# SAME70N21-CU.net
KiCad netlist of a schematic drawn in EAGLE
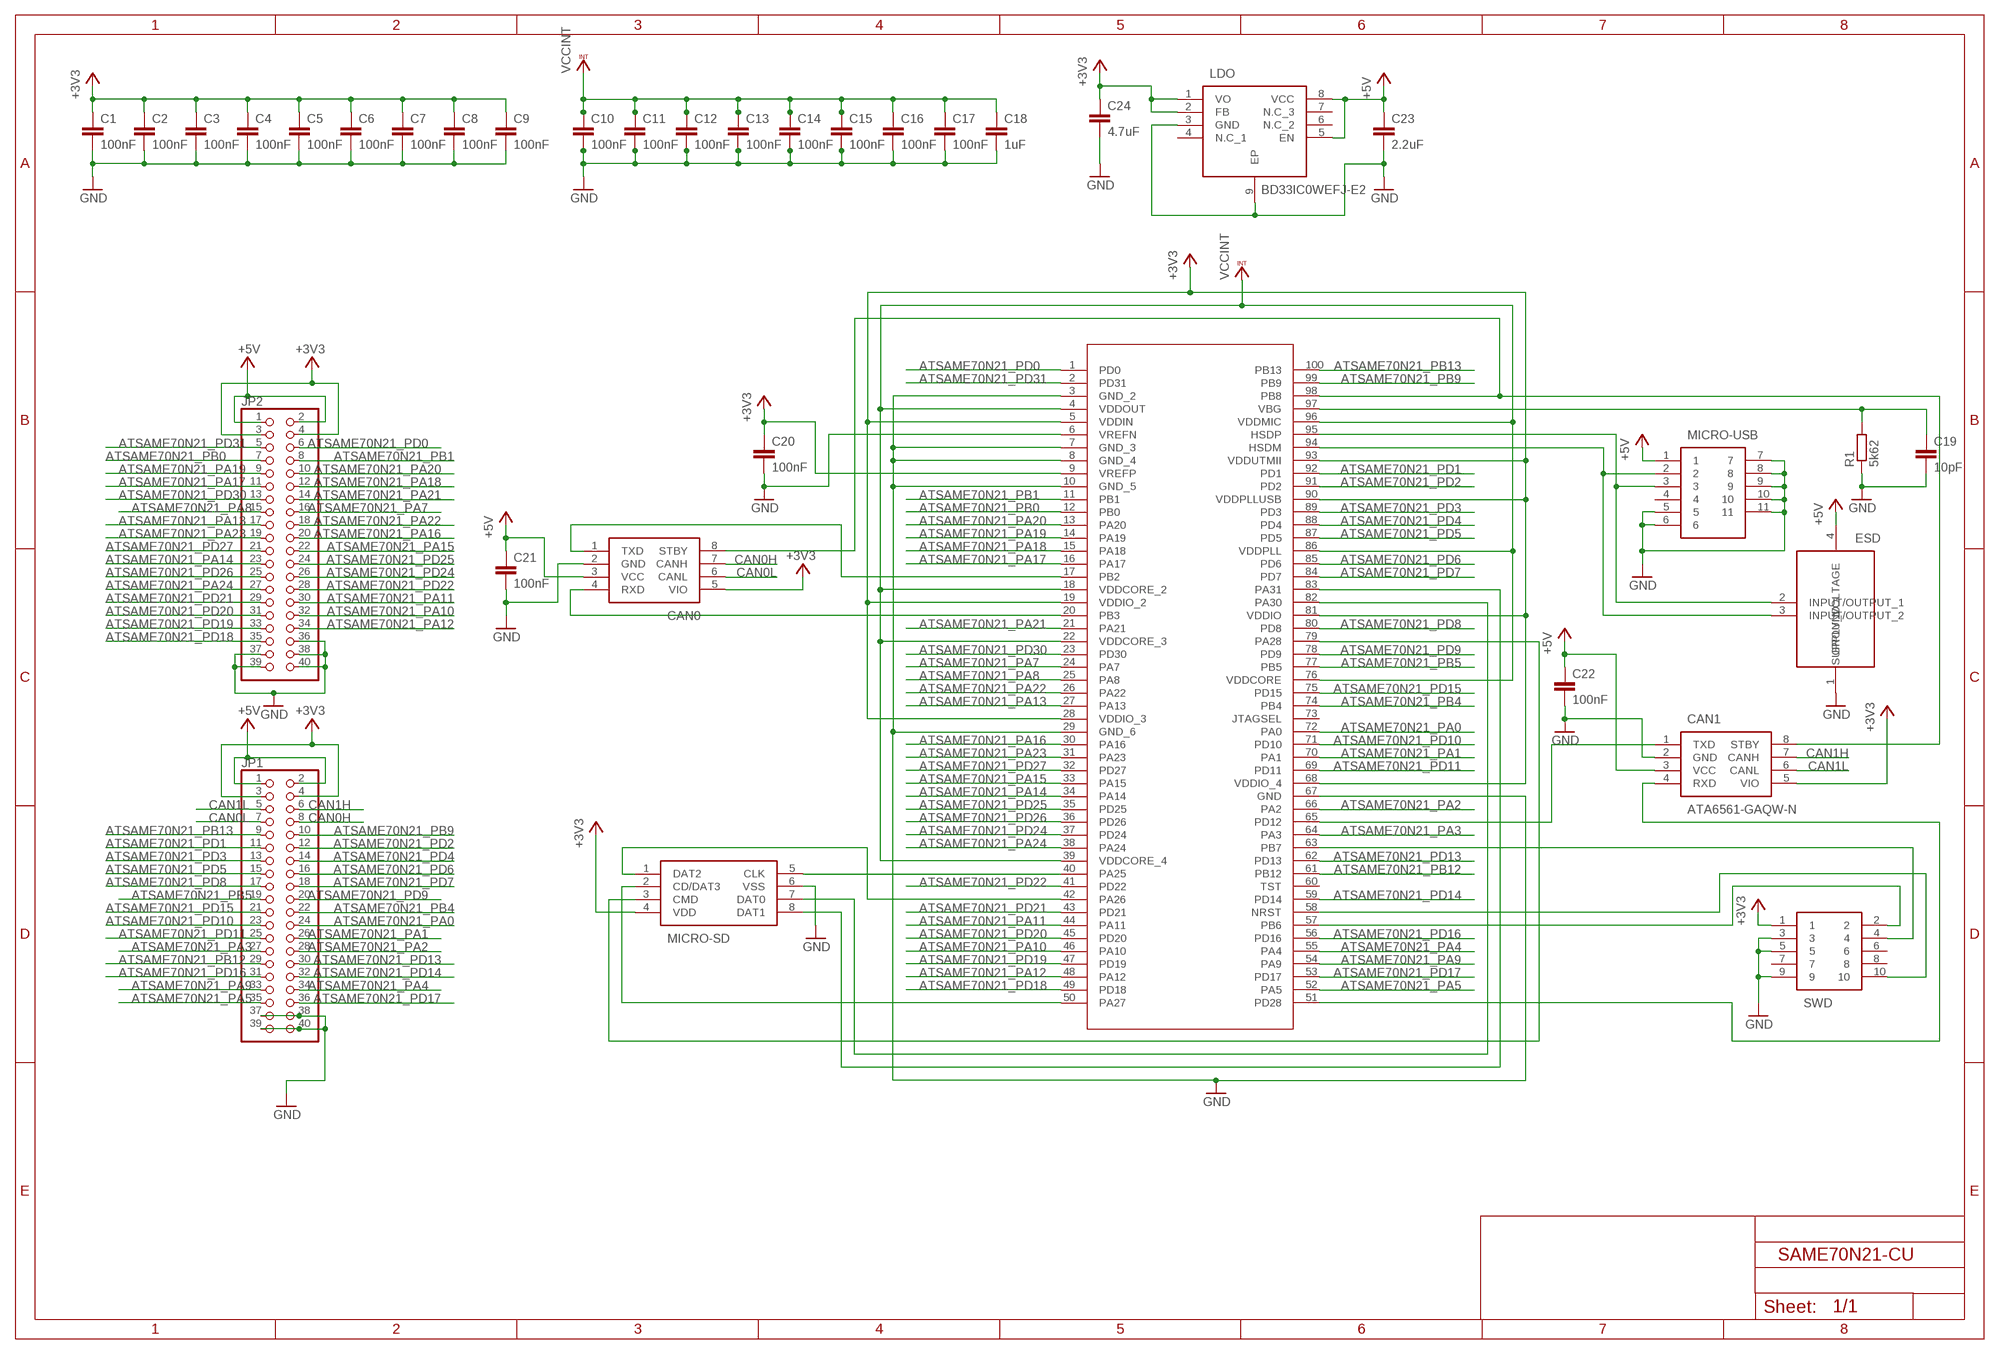
[diagram p0: schematic, sheet 1]

(export (version "E")
  (design (tool "Eeschema 10.0.6"))
  (components
    (comp (ref "C1")
      (value "100nF")
      (footprint "eagle-import:C1206")
      (libsource (lib "eagle-import") (part "C-EUC1206"))
    )
    (comp (ref "C2")
      (value "100nF")
      (footprint "eagle-import:C1206")
      (libsource (lib "eagle-import") (part "C-EUC1206"))
    )
    (comp (ref "C3")
      (value "100nF")
      (footprint "eagle-import:C1206")
      (libsource (lib "eagle-import") (part "C-EUC1206"))
    )
    (comp (ref "C4")
      (value "100nF")
      (footprint "eagle-import:C1206")
      (libsource (lib "eagle-import") (part "C-EUC1206"))
    )
    (comp (ref "C5")
      (value "100nF")
      (footprint "eagle-import:C1206")
      (libsource (lib "eagle-import") (part "C-EUC1206"))
    )
    (comp (ref "C6")
      (value "100nF")
      (footprint "eagle-import:C1206")
      (libsource (lib "eagle-import") (part "C-EUC1206"))
    )
    (comp (ref "C7")
      (value "100nF")
      (footprint "eagle-import:C1206")
      (libsource (lib "eagle-import") (part "C-EUC1206"))
    )
    (comp (ref "C8")
      (value "100nF")
      (footprint "eagle-import:C1206")
      (libsource (lib "eagle-import") (part "C-EUC1206"))
    )
    (comp (ref "C9")
      (value "100nF")
      (footprint "eagle-import:C1206")
      (libsource (lib "eagle-import") (part "C-EUC1206"))
    )
    (comp (ref "C10")
      (value "100nF")
      (footprint "eagle-import:C1206")
      (libsource (lib "eagle-import") (part "C-EUC1206"))
    )
    (comp (ref "C11")
      (value "100nF")
      (footprint "eagle-import:C1206")
      (libsource (lib "eagle-import") (part "C-EUC1206"))
    )
    (comp (ref "C12")
      (value "100nF")
      (footprint "eagle-import:C1206")
      (libsource (lib "eagle-import") (part "C-EUC1206"))
    )
    (comp (ref "C13")
      (value "100nF")
      (footprint "eagle-import:C1206")
      (libsource (lib "eagle-import") (part "C-EUC1206"))
    )
    (comp (ref "C14")
      (value "100nF")
      (footprint "eagle-import:C1206")
      (libsource (lib "eagle-import") (part "C-EUC1206"))
    )
    (comp (ref "C15")
      (value "100nF")
      (footprint "eagle-import:C1206")
      (libsource (lib "eagle-import") (part "C-EUC1206"))
    )
    (comp (ref "C16")
      (value "100nF")
      (footprint "eagle-import:C1206")
      (libsource (lib "eagle-import") (part "C-EUC1206"))
    )
    (comp (ref "C17")
      (value "100nF")
      (footprint "eagle-import:C1206")
      (libsource (lib "eagle-import") (part "C-EUC1206"))
    )
    (comp (ref "C18")
      (value "1uF")
      (footprint "eagle-import:C1206")
      (libsource (lib "eagle-import") (part "C-EUC1206"))
    )
    (comp (ref "C19")
      (value "10pF")
      (footprint "eagle-import:C1206")
      (libsource (lib "eagle-import") (part "C-EUC1206"))
    )
    (comp (ref "C20")
      (value "100nF")
      (footprint "eagle-import:C1206")
      (libsource (lib "eagle-import") (part "C-EUC1206"))
    )
    (comp (ref "C21")
      (value "100nF")
      (footprint "eagle-import:C1206")
      (libsource (lib "eagle-import") (part "C-EUC1206"))
    )
    (comp (ref "C22")
      (value "100nF")
      (footprint "eagle-import:C1206")
      (libsource (lib "eagle-import") (part "C-EUC1206"))
    )
    (comp (ref "C23")
      (value "2.2uF")
      (footprint "eagle-import:C1206")
      (libsource (lib "eagle-import") (part "C-EUC1206"))
    )
    (comp (ref "C24")
      (value "4.7uF")
      (footprint "eagle-import:C1206")
      (libsource (lib "eagle-import") (part "C-EUC1206"))
    )
    (comp (ref "CAN0")
      (value "ATA6561-GAQW-N")
      (footprint "eagle-import:SOIC127P600X175-8N")
      (fields (field (name "MOUSER_PART_NUMBER") "579-ATA6561-GAQW-N"))
      (libsource (lib "eagle-import") (part "ATA6561-GAQW-N"))
    )
    (comp (ref "CAN1")
      (value "ATA6561-GAQW-N")
      (footprint "eagle-import:SOIC127P600X175-8N")
      (fields (field (name "MOUSER_PART_NUMBER") "579-ATA6561-GAQW-N"))
      (libsource (lib "eagle-import") (part "ATA6561-GAQW-N"))
    )
    (comp (ref "ESD")
      (value "PRTR5V0U2X,215")
      (footprint "eagle-import:PRTR5V0U2X")
      (fields (field (name "MOUSER_PART_NUMBER") "771-PRTR5V0U2X-T/R"))
      (libsource (lib "eagle-import") (part "PRTR5V0U2X,215"))
    )
    (comp (ref "JP1")
      (value "PINHD-2X20")
      (footprint "eagle-import:2X20")
      (libsource (lib "eagle-import") (part "PINHD-2X20"))
    )
    (comp (ref "JP2")
      (value "PINHD-2X20")
      (footprint "eagle-import:2X20")
      (libsource (lib "eagle-import") (part "PINHD-2X20"))
    )
    (comp (ref "LDO")
      (value "BD33IC0WEFJ-E2")
      (footprint "eagle-import:SOIC127P600X100-9N")
      (fields (field (name "MOUSER_PART_NUMBER") "755-BD33IC0WEFJ-E2"))
      (libsource (lib "eagle-import") (part "BD33IC0WEFJ-E2"))
    )
    (comp (ref "MICRO-SD")
      (value "104031-0811")
      (footprint "eagle-import:1040310811")
      (fields (field (name "MOUSER_PART_NUMBER") "538-104031-0811"))
      (libsource (lib "eagle-import") (part "104031-0811"))
    )
    (comp (ref "MICRO-USB")
      (value "10118192-0001LF")
      (footprint "eagle-import:101181920001LF")
      (fields (field (name "MOUSER_PART_NUMBER") "649-10118192-0001LF"))
      (libsource (lib "eagle-import") (part "10118192-0001LF"))
    )
    (comp (ref "R1")
      (value "5k62")
      (footprint "eagle-import:R1206")
      (libsource (lib "eagle-import") (part "R-EU_R1206"))
    )
    (comp (ref "SWD")
      (value "62201021121")
      (footprint "eagle-import:WURTH-1.27MM-PITCH-2WAY")
      (fields (field (name "MOUSER_PART_NUMBER") "710-62201021121"))
      (libsource (lib "eagle-import") (part "62201021121"))
    )
    (comp (ref "U1")
      (value "ATSAME70N21A-ANTQFP100_14X14MC_MCH-M")
      (footprint "eagle-import:TQFP100_14X14MC_MCH-M")
      (fields
        (field (name "MANUFACTURER_PART_NUMBER") "ATSAME70N21A-AN")
        (field (name "COPYRIGHT") "Copyright (C) 2022 Ultra Librarian. All rights reserved.")
      )
      (libsource (lib "eagle-import") (part "ATSAME70N21A-ANTQFP100_14X14MC_MCH-M"))
    )
  )
  (nets
    (net (code "1") (name "+3V3") (class "Default")
      (node (ref "C1") (pin "1") (pinfunction "1_1") (pintype "passive"))
      (node (ref "C2") (pin "1") (pinfunction "1_1") (pintype "passive"))
      (node (ref "C20") (pin "1") (pinfunction "1_1") (pintype "passive"))
      (node (ref "C24") (pin "1") (pinfunction "1_1") (pintype "passive"))
      (node (ref "C3") (pin "1") (pinfunction "1_1") (pintype "passive"))
      (node (ref "C4") (pin "1") (pinfunction "1_1") (pintype "passive"))
      (node (ref "C5") (pin "1") (pinfunction "1_1") (pintype "passive"))
      (node (ref "C6") (pin "1") (pinfunction "1_1") (pintype "passive"))
      (node (ref "C7") (pin "1") (pinfunction "1_1") (pintype "passive"))
      (node (ref "C8") (pin "1") (pinfunction "1_1") (pintype "passive"))
      (node (ref "C9") (pin "1") (pinfunction "1_1") (pintype "passive"))
      (node (ref "CAN0") (pin "5") (pinfunction "VIO_5") (pintype "bidirectional"))
      (node (ref "CAN1") (pin "5") (pinfunction "VIO_5") (pintype "bidirectional"))
      (node (ref "JP1") (pin "3") (pinfunction "3_3") (pintype "passive"))
      (node (ref "JP1") (pin "4") (pinfunction "4_4") (pintype "passive"))
      (node (ref "JP2") (pin "3") (pinfunction "3_3") (pintype "passive"))
      (node (ref "JP2") (pin "4") (pinfunction "4_4") (pintype "passive"))
      (node (ref "LDO") (pin "1") (pinfunction "VO_1") (pintype "bidirectional"))
      (node (ref "LDO") (pin "2") (pinfunction "FB_2") (pintype "bidirectional"))
      (node (ref "MICRO-SD") (pin "4") (pinfunction "VDD_4") (pintype "bidirectional"))
      (node (ref "SWD") (pin "1") (pinfunction "1_1") (pintype "bidirectional"))
      (node (ref "U1") (pin "19") (pinfunction "VDDIO_2_19") (pintype "power_in"))
      (node (ref "U1") (pin "28") (pinfunction "VDDIO_3_28") (pintype "power_in"))
      (node (ref "U1") (pin "5") (pinfunction "VDDIN_5") (pintype "power_in"))
      (node (ref "U1") (pin "68") (pinfunction "VDDIO_4_68") (pintype "power_in"))
      (node (ref "U1") (pin "81") (pinfunction "VDDIO_81") (pintype "power_in"))
      (node (ref "U1") (pin "9") (pinfunction "VREFP_9") (pintype "power_in"))
      (node (ref "U1") (pin "90") (pinfunction "VDDPLLUSB_90") (pintype "power_in"))
      (node (ref "U1") (pin "93") (pinfunction "VDDUTMII_93") (pintype "power_in"))
    )
    (net (code "2") (name "+5V") (class "Default")
      (node (ref "C21") (pin "1") (pinfunction "1_1") (pintype "passive"))
      (node (ref "C22") (pin "1") (pinfunction "1_1") (pintype "passive"))
      (node (ref "C23") (pin "1") (pinfunction "1_1") (pintype "passive"))
      (node (ref "CAN0") (pin "3") (pinfunction "VCC_3") (pintype "bidirectional"))
      (node (ref "CAN1") (pin "3") (pinfunction "VCC_3") (pintype "bidirectional"))
      (node (ref "ESD") (pin "4") (pinfunction "SUPPLY_VOLTAGE_4") (pintype "bidirectional"))
      (node (ref "JP1") (pin "1") (pinfunction "1_1") (pintype "passive"))
      (node (ref "JP1") (pin "2") (pinfunction "2_2") (pintype "passive"))
      (node (ref "JP2") (pin "1") (pinfunction "1_1") (pintype "passive"))
      (node (ref "JP2") (pin "2") (pinfunction "2_2") (pintype "passive"))
      (node (ref "LDO") (pin "5") (pinfunction "EN_5") (pintype "bidirectional"))
      (node (ref "LDO") (pin "8") (pinfunction "VCC_8") (pintype "bidirectional"))
      (node (ref "MICRO-USB") (pin "1") (pinfunction "1_1") (pintype "bidirectional"))
    )
    (net (code "3") (name "/ATSAME70N21_PA0") (class "Default")
      (node (ref "JP1") (pin "24") (pinfunction "24_24") (pintype "passive"))
      (node (ref "U1") (pin "72") (pinfunction "PA0_72") (pintype "bidirectional"))
    )
    (net (code "4") (name "/ATSAME70N21_PA1") (class "Default")
      (node (ref "JP1") (pin "26") (pinfunction "26_26") (pintype "passive"))
      (node (ref "U1") (pin "70") (pinfunction "PA1_70") (pintype "bidirectional"))
    )
    (net (code "5") (name "/ATSAME70N21_PA2") (class "Default")
      (node (ref "JP1") (pin "28") (pinfunction "28_28") (pintype "passive"))
      (node (ref "U1") (pin "66") (pinfunction "PA2_66") (pintype "bidirectional"))
    )
    (net (code "6") (name "/ATSAME70N21_PA3") (class "Default")
      (node (ref "JP1") (pin "27") (pinfunction "27_27") (pintype "passive"))
      (node (ref "U1") (pin "64") (pinfunction "PA3_64") (pintype "bidirectional"))
    )
    (net (code "7") (name "/ATSAME70N21_PA4") (class "Default")
      (node (ref "JP1") (pin "34") (pinfunction "34_34") (pintype "passive"))
      (node (ref "U1") (pin "55") (pinfunction "PA4_55") (pintype "bidirectional"))
    )
    (net (code "8") (name "/ATSAME70N21_PA5") (class "Default")
      (node (ref "JP1") (pin "35") (pinfunction "35_35") (pintype "passive"))
      (node (ref "U1") (pin "52") (pinfunction "PA5_52") (pintype "bidirectional"))
    )
    (net (code "9") (name "/ATSAME70N21_PA7") (class "Default")
      (node (ref "JP2") (pin "16") (pinfunction "16_16") (pintype "passive"))
      (node (ref "U1") (pin "24") (pinfunction "PA7_24") (pintype "bidirectional"))
    )
    (net (code "10") (name "/ATSAME70N21_PA8") (class "Default")
      (node (ref "JP2") (pin "15") (pinfunction "15_15") (pintype "passive"))
      (node (ref "U1") (pin "25") (pinfunction "PA8_25") (pintype "bidirectional"))
    )
    (net (code "11") (name "/ATSAME70N21_PA9") (class "Default")
      (node (ref "JP1") (pin "33") (pinfunction "33_33") (pintype "passive"))
      (node (ref "U1") (pin "54") (pinfunction "PA9_54") (pintype "bidirectional"))
    )
    (net (code "12") (name "/ATSAME70N21_PA10") (class "Default")
      (node (ref "JP2") (pin "32") (pinfunction "32_32") (pintype "passive"))
      (node (ref "U1") (pin "46") (pinfunction "PA10_46") (pintype "bidirectional"))
    )
    (net (code "13") (name "/ATSAME70N21_PA11") (class "Default")
      (node (ref "JP2") (pin "30") (pinfunction "30_30") (pintype "passive"))
      (node (ref "U1") (pin "44") (pinfunction "PA11_44") (pintype "bidirectional"))
    )
    (net (code "14") (name "/ATSAME70N21_PA12") (class "Default")
      (node (ref "JP2") (pin "34") (pinfunction "34_34") (pintype "passive"))
      (node (ref "U1") (pin "48") (pinfunction "PA12_48") (pintype "bidirectional"))
    )
    (net (code "15") (name "/ATSAME70N21_PA13") (class "Default")
      (node (ref "JP2") (pin "17") (pinfunction "17_17") (pintype "passive"))
      (node (ref "U1") (pin "27") (pinfunction "PA13_27") (pintype "bidirectional"))
    )
    (net (code "16") (name "/ATSAME70N21_PA14") (class "Default")
      (node (ref "JP2") (pin "23") (pinfunction "23_23") (pintype "passive"))
      (node (ref "U1") (pin "34") (pinfunction "PA14_34") (pintype "bidirectional"))
    )
    (net (code "17") (name "/ATSAME70N21_PA15") (class "Default")
      (node (ref "JP2") (pin "22") (pinfunction "22_22") (pintype "passive"))
      (node (ref "U1") (pin "33") (pinfunction "PA15_33") (pintype "bidirectional"))
    )
    (net (code "18") (name "/ATSAME70N21_PA16") (class "Default")
      (node (ref "JP2") (pin "20") (pinfunction "20_20") (pintype "passive"))
      (node (ref "U1") (pin "30") (pinfunction "PA16_30") (pintype "bidirectional"))
    )
    (net (code "19") (name "/ATSAME70N21_PA17") (class "Default")
      (node (ref "JP2") (pin "11") (pinfunction "11_11") (pintype "passive"))
      (node (ref "U1") (pin "16") (pinfunction "PA17_16") (pintype "bidirectional"))
    )
    (net (code "20") (name "/ATSAME70N21_PA18") (class "Default")
      (node (ref "JP2") (pin "12") (pinfunction "12_12") (pintype "passive"))
      (node (ref "U1") (pin "15") (pinfunction "PA18_15") (pintype "bidirectional"))
    )
    (net (code "21") (name "/ATSAME70N21_PA19") (class "Default")
      (node (ref "JP2") (pin "9") (pinfunction "9_9") (pintype "passive"))
      (node (ref "U1") (pin "14") (pinfunction "PA19_14") (pintype "bidirectional"))
    )
    (net (code "22") (name "/ATSAME70N21_PA20") (class "Default")
      (node (ref "JP2") (pin "10") (pinfunction "10_10") (pintype "passive"))
      (node (ref "U1") (pin "13") (pinfunction "PA20_13") (pintype "bidirectional"))
    )
    (net (code "23") (name "/ATSAME70N21_PA21") (class "Default")
      (node (ref "JP2") (pin "14") (pinfunction "14_14") (pintype "passive"))
      (node (ref "U1") (pin "21") (pinfunction "PA21_21") (pintype "bidirectional"))
    )
    (net (code "24") (name "/ATSAME70N21_PA22") (class "Default")
      (node (ref "JP2") (pin "18") (pinfunction "18_18") (pintype "passive"))
      (node (ref "U1") (pin "26") (pinfunction "PA22_26") (pintype "bidirectional"))
    )
    (net (code "25") (name "/ATSAME70N21_PA23") (class "Default")
      (node (ref "JP2") (pin "19") (pinfunction "19_19") (pintype "passive"))
      (node (ref "U1") (pin "31") (pinfunction "PA23_31") (pintype "bidirectional"))
    )
    (net (code "26") (name "/ATSAME70N21_PA24") (class "Default")
      (node (ref "JP2") (pin "27") (pinfunction "27_27") (pintype "passive"))
      (node (ref "U1") (pin "38") (pinfunction "PA24_38") (pintype "bidirectional"))
    )
    (net (code "27") (name "/ATSAME70N21_PB0") (class "Default")
      (node (ref "JP2") (pin "7") (pinfunction "7_7") (pintype "passive"))
      (node (ref "U1") (pin "12") (pinfunction "PB0_12") (pintype "bidirectional"))
    )
    (net (code "28") (name "/ATSAME70N21_PB1") (class "Default")
      (node (ref "JP2") (pin "8") (pinfunction "8_8") (pintype "passive"))
      (node (ref "U1") (pin "11") (pinfunction "PB1_11") (pintype "bidirectional"))
    )
    (net (code "29") (name "/ATSAME70N21_PB4") (class "Default")
      (node (ref "JP1") (pin "22") (pinfunction "22_22") (pintype "passive"))
      (node (ref "U1") (pin "74") (pinfunction "PB4_74") (pintype "bidirectional"))
    )
    (net (code "30") (name "/ATSAME70N21_PB5") (class "Default")
      (node (ref "JP1") (pin "19") (pinfunction "19_19") (pintype "passive"))
      (node (ref "U1") (pin "77") (pinfunction "PB5_77") (pintype "bidirectional"))
    )
    (net (code "31") (name "/ATSAME70N21_PB9") (class "Default")
      (node (ref "JP1") (pin "10") (pinfunction "10_10") (pintype "passive"))
      (node (ref "U1") (pin "99") (pinfunction "PB9_99") (pintype "bidirectional"))
    )
    (net (code "32") (name "/ATSAME70N21_PB12") (class "Default")
      (node (ref "JP1") (pin "29") (pinfunction "29_29") (pintype "passive"))
      (node (ref "U1") (pin "61") (pinfunction "PB12_61") (pintype "bidirectional"))
    )
    (net (code "33") (name "/ATSAME70N21_PB13") (class "Default")
      (node (ref "JP1") (pin "9") (pinfunction "9_9") (pintype "passive"))
      (node (ref "U1") (pin "100") (pinfunction "PB13_100") (pintype "bidirectional"))
    )
    (net (code "34") (name "/ATSAME70N21_PD0") (class "Default")
      (node (ref "JP2") (pin "6") (pinfunction "6_6") (pintype "passive"))
      (node (ref "U1") (pin "1") (pinfunction "PD0_1") (pintype "bidirectional"))
    )
    (net (code "35") (name "/ATSAME70N21_PD1") (class "Default")
      (node (ref "JP1") (pin "11") (pinfunction "11_11") (pintype "passive"))
      (node (ref "U1") (pin "92") (pinfunction "PD1_92") (pintype "bidirectional"))
    )
    (net (code "36") (name "/ATSAME70N21_PD2") (class "Default")
      (node (ref "JP1") (pin "12") (pinfunction "12_12") (pintype "passive"))
      (node (ref "U1") (pin "91") (pinfunction "PD2_91") (pintype "bidirectional"))
    )
    (net (code "37") (name "/ATSAME70N21_PD3") (class "Default")
      (node (ref "JP1") (pin "13") (pinfunction "13_13") (pintype "passive"))
      (node (ref "U1") (pin "89") (pinfunction "PD3_89") (pintype "bidirectional"))
    )
    (net (code "38") (name "/ATSAME70N21_PD4") (class "Default")
      (node (ref "JP1") (pin "14") (pinfunction "14_14") (pintype "passive"))
      (node (ref "U1") (pin "88") (pinfunction "PD4_88") (pintype "bidirectional"))
    )
    (net (code "39") (name "/ATSAME70N21_PD5") (class "Default")
      (node (ref "JP1") (pin "15") (pinfunction "15_15") (pintype "passive"))
      (node (ref "U1") (pin "87") (pinfunction "PD5_87") (pintype "bidirectional"))
    )
    (net (code "40") (name "/ATSAME70N21_PD6") (class "Default")
      (node (ref "JP1") (pin "16") (pinfunction "16_16") (pintype "passive"))
      (node (ref "U1") (pin "85") (pinfunction "PD6_85") (pintype "bidirectional"))
    )
    (net (code "41") (name "/ATSAME70N21_PD7") (class "Default")
      (node (ref "JP1") (pin "18") (pinfunction "18_18") (pintype "passive"))
      (node (ref "U1") (pin "84") (pinfunction "PD7_84") (pintype "bidirectional"))
    )
    (net (code "42") (name "/ATSAME70N21_PD8") (class "Default")
      (node (ref "JP1") (pin "17") (pinfunction "17_17") (pintype "passive"))
      (node (ref "U1") (pin "80") (pinfunction "PD8_80") (pintype "bidirectional"))
    )
    (net (code "43") (name "/ATSAME70N21_PD9") (class "Default")
      (node (ref "JP1") (pin "20") (pinfunction "20_20") (pintype "passive"))
      (node (ref "U1") (pin "78") (pinfunction "PD9_78") (pintype "bidirectional"))
    )
    (net (code "44") (name "/ATSAME70N21_PD10") (class "Default")
      (node (ref "JP1") (pin "23") (pinfunction "23_23") (pintype "passive"))
      (node (ref "U1") (pin "71") (pinfunction "PD10_71") (pintype "bidirectional"))
    )
    (net (code "45") (name "/ATSAME70N21_PD11") (class "Default")
      (node (ref "JP1") (pin "25") (pinfunction "25_25") (pintype "passive"))
      (node (ref "U1") (pin "69") (pinfunction "PD11_69") (pintype "bidirectional"))
    )
    (net (code "46") (name "/ATSAME70N21_PD13") (class "Default")
      (node (ref "JP1") (pin "30") (pinfunction "30_30") (pintype "passive"))
      (node (ref "U1") (pin "62") (pinfunction "PD13_62") (pintype "bidirectional"))
    )
    (net (code "47") (name "/ATSAME70N21_PD14") (class "Default")
      (node (ref "JP1") (pin "32") (pinfunction "32_32") (pintype "passive"))
      (node (ref "U1") (pin "59") (pinfunction "PD14_59") (pintype "bidirectional"))
    )
    (net (code "48") (name "/ATSAME70N21_PD15") (class "Default")
      (node (ref "JP1") (pin "21") (pinfunction "21_21") (pintype "passive"))
      (node (ref "U1") (pin "75") (pinfunction "PD15_75") (pintype "bidirectional"))
    )
    (net (code "49") (name "/ATSAME70N21_PD16") (class "Default")
      (node (ref "JP1") (pin "31") (pinfunction "31_31") (pintype "passive"))
      (node (ref "U1") (pin "56") (pinfunction "PD16_56") (pintype "bidirectional"))
    )
    (net (code "50") (name "/ATSAME70N21_PD17") (class "Default")
      (node (ref "JP1") (pin "36") (pinfunction "36_36") (pintype "passive"))
      (node (ref "U1") (pin "53") (pinfunction "PD17_53") (pintype "bidirectional"))
    )
    (net (code "51") (name "/ATSAME70N21_PD18") (class "Default")
      (node (ref "JP2") (pin "35") (pinfunction "35_35") (pintype "passive"))
      (node (ref "U1") (pin "49") (pinfunction "PD18_49") (pintype "bidirectional"))
    )
    (net (code "52") (name "/ATSAME70N21_PD19") (class "Default")
      (node (ref "JP2") (pin "33") (pinfunction "33_33") (pintype "passive"))
      (node (ref "U1") (pin "47") (pinfunction "PD19_47") (pintype "bidirectional"))
    )
    (net (code "53") (name "/ATSAME70N21_PD20") (class "Default")
      (node (ref "JP2") (pin "31") (pinfunction "31_31") (pintype "passive"))
      (node (ref "U1") (pin "45") (pinfunction "PD20_45") (pintype "bidirectional"))
    )
    (net (code "54") (name "/ATSAME70N21_PD21") (class "Default")
      (node (ref "JP2") (pin "29") (pinfunction "29_29") (pintype "passive"))
      (node (ref "U1") (pin "43") (pinfunction "PD21_43") (pintype "bidirectional"))
    )
    (net (code "55") (name "/ATSAME70N21_PD22") (class "Default")
      (node (ref "JP2") (pin "28") (pinfunction "28_28") (pintype "passive"))
      (node (ref "U1") (pin "41") (pinfunction "PD22_41") (pintype "bidirectional"))
    )
    (net (code "56") (name "/ATSAME70N21_PD24") (class "Default")
      (node (ref "JP2") (pin "26") (pinfunction "26_26") (pintype "passive"))
      (node (ref "U1") (pin "37") (pinfunction "PD24_37") (pintype "bidirectional"))
    )
    (net (code "57") (name "/ATSAME70N21_PD25") (class "Default")
      (node (ref "JP2") (pin "24") (pinfunction "24_24") (pintype "passive"))
      (node (ref "U1") (pin "35") (pinfunction "PD25_35") (pintype "bidirectional"))
    )
    (net (code "58") (name "/ATSAME70N21_PD26") (class "Default")
      (node (ref "JP2") (pin "25") (pinfunction "25_25") (pintype "passive"))
      (node (ref "U1") (pin "36") (pinfunction "PD26_36") (pintype "bidirectional"))
    )
    (net (code "59") (name "/ATSAME70N21_PD27") (class "Default")
      (node (ref "JP2") (pin "21") (pinfunction "21_21") (pintype "passive"))
      (node (ref "U1") (pin "32") (pinfunction "PD27_32") (pintype "bidirectional"))
    )
    (net (code "60") (name "/ATSAME70N21_PD30") (class "Default")
      (node (ref "JP2") (pin "13") (pinfunction "13_13") (pintype "passive"))
      (node (ref "U1") (pin "23") (pinfunction "PD30_23") (pintype "bidirectional"))
    )
    (net (code "61") (name "/ATSAME70N21_PD31") (class "Default")
      (node (ref "JP2") (pin "5") (pinfunction "5_5") (pintype "passive"))
      (node (ref "U1") (pin "2") (pinfunction "PD31_2") (pintype "bidirectional"))
    )
    (net (code "62") (name "/CAN0H") (class "Default")
      (node (ref "CAN0") (pin "7") (pinfunction "CANH_7") (pintype "bidirectional"))
      (node (ref "JP1") (pin "8") (pinfunction "8_8") (pintype "passive"))
    )
    (net (code "63") (name "/CAN0L") (class "Default")
      (node (ref "CAN0") (pin "6") (pinfunction "CANL_6") (pintype "bidirectional"))
      (node (ref "JP1") (pin "7") (pinfunction "7_7") (pintype "passive"))
    )
    (net (code "64") (name "/CAN1H") (class "Default")
      (node (ref "CAN1") (pin "7") (pinfunction "CANH_7") (pintype "bidirectional"))
      (node (ref "JP1") (pin "6") (pinfunction "6_6") (pintype "passive"))
    )
    (net (code "65") (name "/CAN1L") (class "Default")
      (node (ref "CAN1") (pin "6") (pinfunction "CANL_6") (pintype "bidirectional"))
      (node (ref "JP1") (pin "5") (pinfunction "5_5") (pintype "passive"))
    )
    (net (code "66") (name "GND") (class "Default")
      (node (ref "C1") (pin "2") (pinfunction "2_2") (pintype "passive"))
      (node (ref "C10") (pin "2") (pinfunction "2_2") (pintype "passive"))
      (node (ref "C11") (pin "2") (pinfunction "2_2") (pintype "passive"))
      (node (ref "C12") (pin "2") (pinfunction "2_2") (pintype "passive"))
      (node (ref "C13") (pin "2") (pinfunction "2_2") (pintype "passive"))
      (node (ref "C14") (pin "2") (pinfunction "2_2") (pintype "passive"))
      (node (ref "C15") (pin "2") (pinfunction "2_2") (pintype "passive"))
      (node (ref "C16") (pin "2") (pinfunction "2_2") (pintype "passive"))
      (node (ref "C17") (pin "2") (pinfunction "2_2") (pintype "passive"))
      (node (ref "C18") (pin "2") (pinfunction "2_2") (pintype "passive"))
      (node (ref "C19") (pin "2") (pinfunction "2_2") (pintype "passive"))
      (node (ref "C2") (pin "2") (pinfunction "2_2") (pintype "passive"))
      (node (ref "C20") (pin "2") (pinfunction "2_2") (pintype "passive"))
      (node (ref "C21") (pin "2") (pinfunction "2_2") (pintype "passive"))
      (node (ref "C22") (pin "2") (pinfunction "2_2") (pintype "passive"))
      (node (ref "C23") (pin "2") (pinfunction "2_2") (pintype "passive"))
      (node (ref "C24") (pin "2") (pinfunction "2_2") (pintype "passive"))
      (node (ref "C3") (pin "2") (pinfunction "2_2") (pintype "passive"))
      (node (ref "C4") (pin "2") (pinfunction "2_2") (pintype "passive"))
      (node (ref "C5") (pin "2") (pinfunction "2_2") (pintype "passive"))
      (node (ref "C6") (pin "2") (pinfunction "2_2") (pintype "passive"))
      (node (ref "C7") (pin "2") (pinfunction "2_2") (pintype "passive"))
      (node (ref "C8") (pin "2") (pinfunction "2_2") (pintype "passive"))
      (node (ref "C9") (pin "2") (pinfunction "2_2") (pintype "passive"))
      (node (ref "CAN0") (pin "2") (pinfunction "GND_2") (pintype "bidirectional"))
      (node (ref "CAN1") (pin "2") (pinfunction "GND_2") (pintype "bidirectional"))
      (node (ref "ESD") (pin "1") (pinfunction "GROUND_1") (pintype "bidirectional"))
      (node (ref "JP1") (pin "37") (pinfunction "37_37") (pintype "passive"))
      (node (ref "JP1") (pin "38") (pinfunction "38_38") (pintype "passive"))
      (node (ref "JP1") (pin "39") (pinfunction "39_39") (pintype "passive"))
      (node (ref "JP1") (pin "40") (pinfunction "40_40") (pintype "passive"))
      (node (ref "JP2") (pin "36") (pinfunction "36_36") (pintype "passive"))
      (node (ref "JP2") (pin "37") (pinfunction "37_37") (pintype "passive"))
      (node (ref "JP2") (pin "38") (pinfunction "38_38") (pintype "passive"))
      (node (ref "JP2") (pin "39") (pinfunction "39_39") (pintype "passive"))
      (node (ref "JP2") (pin "40") (pinfunction "40_40") (pintype "passive"))
      (node (ref "LDO") (pin "3") (pinfunction "GND_3") (pintype "bidirectional"))
      (node (ref "LDO") (pin "9") (pinfunction "EP_9") (pintype "bidirectional"))
      (node (ref "MICRO-SD") (pin "6") (pinfunction "VSS_6") (pintype "bidirectional"))
      (node (ref "MICRO-USB") (pin "10") (pinfunction "10_10") (pintype "bidirectional"))
      (node (ref "MICRO-USB") (pin "11") (pinfunction "11_11") (pintype "bidirectional"))
      (node (ref "MICRO-USB") (pin "5") (pinfunction "5_5") (pintype "bidirectional"))
      (node (ref "MICRO-USB") (pin "6") (pinfunction "6_6") (pintype "bidirectional"))
      (node (ref "MICRO-USB") (pin "7") (pinfunction "7_7") (pintype "bidirectional"))
      (node (ref "MICRO-USB") (pin "8") (pinfunction "8_8") (pintype "bidirectional"))
      (node (ref "MICRO-USB") (pin "9") (pinfunction "9_9") (pintype "bidirectional"))
      (node (ref "R1") (pin "1") (pinfunction "1_1") (pintype "passive"))
      (node (ref "SWD") (pin "3") (pinfunction "3_3") (pintype "bidirectional"))
      (node (ref "SWD") (pin "5") (pinfunction "5_5") (pintype "bidirectional"))
      (node (ref "SWD") (pin "9") (pinfunction "9_9") (pintype "bidirectional"))
      (node (ref "U1") (pin "10") (pinfunction "GND_5_10") (pintype "passive"))
      (node (ref "U1") (pin "29") (pinfunction "GND_6_29") (pintype "passive"))
      (node (ref "U1") (pin "3") (pinfunction "GND_2_3") (pintype "passive"))
      (node (ref "U1") (pin "6") (pinfunction "VREFN_6") (pintype "power_in"))
      (node (ref "U1") (pin "67") (pinfunction "GND_67") (pintype "passive"))
      (node (ref "U1") (pin "7") (pinfunction "GND_3_7") (pintype "passive"))
      (node (ref "U1") (pin "8") (pinfunction "GND_4_8") (pintype "passive"))
    )
    (net (code "67") (name "Net-(CAN0-RXD)") (class "Default")
      (node (ref "CAN0") (pin "4") (pinfunction "RXD_4") (pintype "bidirectional"))
      (node (ref "U1") (pin "20") (pinfunction "PB3_20") (pintype "bidirectional"))
    )
    (net (code "68") (name "Net-(CAN0-STBY)") (class "Default")
      (node (ref "CAN0") (pin "8") (pinfunction "STBY_8") (pintype "bidirectional"))
      (node (ref "CAN1") (pin "8") (pinfunction "STBY_8") (pintype "bidirectional"))
      (node (ref "U1") (pin "98") (pinfunction "PB8_98") (pintype "bidirectional"))
    )
    (net (code "69") (name "Net-(CAN0-TXD)") (class "Default")
      (node (ref "CAN0") (pin "1") (pinfunction "TXD_1") (pintype "bidirectional"))
      (node (ref "U1") (pin "17") (pinfunction "PB2_17") (pintype "bidirectional"))
    )
    (net (code "70") (name "Net-(CAN1-RXD)") (class "Default")
      (node (ref "CAN1") (pin "4") (pinfunction "RXD_4") (pintype "bidirectional"))
      (node (ref "U1") (pin "51") (pinfunction "PD28_51") (pintype "bidirectional"))
    )
    (net (code "71") (name "Net-(CAN1-TXD)") (class "Default")
      (node (ref "CAN1") (pin "1") (pinfunction "TXD_1") (pintype "bidirectional"))
      (node (ref "U1") (pin "65") (pinfunction "PD12_65") (pintype "bidirectional"))
    )
    (net (code "72") (name "Net-(ESD-INPUT{slash}OUTPUT_1)") (class "Default")
      (node (ref "ESD") (pin "2") (pinfunction "INPUT/OUTPUT_1_2") (pintype "bidirectional"))
      (node (ref "MICRO-USB") (pin "3") (pinfunction "3_3") (pintype "bidirectional"))
      (node (ref "U1") (pin "95") (pinfunction "HSDP_95") (pintype "passive"))
    )
    (net (code "73") (name "Net-(ESD-INPUT{slash}OUTPUT_2)") (class "Default")
      (node (ref "ESD") (pin "3") (pinfunction "INPUT/OUTPUT_2_3") (pintype "bidirectional"))
      (node (ref "MICRO-USB") (pin "2") (pinfunction "2_2") (pintype "bidirectional"))
      (node (ref "U1") (pin "94") (pinfunction "HSDM_94") (pintype "passive"))
    )
    (net (code "74") (name "Net-(MICRO-SD-CD{slash}DAT3)") (class "Default")
      (node (ref "MICRO-SD") (pin "2") (pinfunction "CD/DAT3_2") (pintype "bidirectional"))
      (node (ref "U1") (pin "50") (pinfunction "PA27_50") (pintype "bidirectional"))
    )
    (net (code "75") (name "Net-(MICRO-SD-CLK)") (class "Default")
      (node (ref "MICRO-SD") (pin "5") (pinfunction "CLK_5") (pintype "bidirectional"))
      (node (ref "U1") (pin "40") (pinfunction "PA25_40") (pintype "bidirectional"))
    )
    (net (code "76") (name "Net-(MICRO-SD-CMD)") (class "Default")
      (node (ref "MICRO-SD") (pin "3") (pinfunction "CMD_3") (pintype "bidirectional"))
      (node (ref "U1") (pin "79") (pinfunction "PA28_79") (pintype "bidirectional"))
    )
    (net (code "77") (name "Net-(MICRO-SD-DAT0)") (class "Default")
      (node (ref "MICRO-SD") (pin "7") (pinfunction "DAT0_7") (pintype "bidirectional"))
      (node (ref "U1") (pin "82") (pinfunction "PA30_82") (pintype "bidirectional"))
    )
    (net (code "78") (name "Net-(MICRO-SD-DAT1)") (class "Default")
      (node (ref "MICRO-SD") (pin "8") (pinfunction "DAT1_8") (pintype "bidirectional"))
      (node (ref "U1") (pin "83") (pinfunction "PA31_83") (pintype "bidirectional"))
    )
    (net (code "79") (name "Net-(MICRO-SD-DAT2)") (class "Default")
      (node (ref "MICRO-SD") (pin "1") (pinfunction "DAT2_1") (pintype "bidirectional"))
      (node (ref "U1") (pin "42") (pinfunction "PA26_42") (pintype "bidirectional"))
    )
    (net (code "80") (name "Net-(U1-NRST)") (class "Default")
      (node (ref "SWD") (pin "10") (pinfunction "10_10") (pintype "bidirectional"))
      (node (ref "U1") (pin "58") (pinfunction "NRST_58") (pintype "passive"))
    )
    (net (code "81") (name "Net-(U1-PB6)") (class "Default")
      (node (ref "SWD") (pin "2") (pinfunction "2_2") (pintype "bidirectional"))
      (node (ref "U1") (pin "57") (pinfunction "PB6_57") (pintype "bidirectional"))
    )
    (net (code "82") (name "Net-(U1-PB7)") (class "Default")
      (node (ref "SWD") (pin "4") (pinfunction "4_4") (pintype "bidirectional"))
      (node (ref "U1") (pin "63") (pinfunction "PB7_63") (pintype "bidirectional"))
    )
    (net (code "83") (name "Net-(U1-VBG)") (class "Default")
      (node (ref "C19") (pin "1") (pinfunction "1_1") (pintype "passive"))
      (node (ref "R1") (pin "2") (pinfunction "2_2") (pintype "passive"))
      (node (ref "U1") (pin "97") (pinfunction "VBG_97") (pintype "passive"))
    )
    (net (code "84") (name "VCCINT") (class "Default")
      (node (ref "C10") (pin "1") (pinfunction "1_1") (pintype "passive"))
      (node (ref "C11") (pin "1") (pinfunction "1_1") (pintype "passive"))
      (node (ref "C12") (pin "1") (pinfunction "1_1") (pintype "passive"))
      (node (ref "C13") (pin "1") (pinfunction "1_1") (pintype "passive"))
      (node (ref "C14") (pin "1") (pinfunction "1_1") (pintype "passive"))
      (node (ref "C15") (pin "1") (pinfunction "1_1") (pintype "passive"))
      (node (ref "C16") (pin "1") (pinfunction "1_1") (pintype "passive"))
      (node (ref "C17") (pin "1") (pinfunction "1_1") (pintype "passive"))
      (node (ref "C18") (pin "1") (pinfunction "1_1") (pintype "passive"))
      (node (ref "U1") (pin "18") (pinfunction "VDDCORE_2_18") (pintype "power_in"))
      (node (ref "U1") (pin "22") (pinfunction "VDDCORE_3_22") (pintype "power_in"))
      (node (ref "U1") (pin "39") (pinfunction "VDDCORE_4_39") (pintype "power_in"))
      (node (ref "U1") (pin "4") (pinfunction "VDDOUT_4") (pintype "output"))
      (node (ref "U1") (pin "76") (pinfunction "VDDCORE_76") (pintype "power_in"))
      (node (ref "U1") (pin "86") (pinfunction "VDDPLL_86") (pintype "power_in"))
      (node (ref "U1") (pin "96") (pinfunction "VDDMIC_96") (pintype "power_in"))
    )
    (net (code "85") (name "unconnected-(LDO-N.C_1-Pad4)") (class "Default")
      (node (ref "LDO") (pin "4") (pinfunction "N.C_1_4") (pintype "bidirectional"))
    )
    (net (code "86") (name "unconnected-(LDO-N.C_2-Pad6)") (class "Default")
      (node (ref "LDO") (pin "6") (pinfunction "N.C_2_6") (pintype "bidirectional"))
    )
    (net (code "87") (name "unconnected-(LDO-N.C_3-Pad7)") (class "Default")
      (node (ref "LDO") (pin "7") (pinfunction "N.C_3_7") (pintype "bidirectional"))
    )
    (net (code "88") (name "unconnected-(MICRO-USB-Pad4)") (class "Default")
      (node (ref "MICRO-USB") (pin "4") (pinfunction "4_4") (pintype "bidirectional"))
    )
    (net (code "89") (name "unconnected-(SWD-Pad6)") (class "Default")
      (node (ref "SWD") (pin "6") (pinfunction "6_6") (pintype "bidirectional"))
    )
    (net (code "90") (name "unconnected-(SWD-Pad7)") (class "Default")
      (node (ref "SWD") (pin "7") (pinfunction "7_7") (pintype "bidirectional"))
    )
    (net (code "91") (name "unconnected-(SWD-Pad8)") (class "Default")
      (node (ref "SWD") (pin "8") (pinfunction "8_8") (pintype "bidirectional"))
    )
    (net (code "92") (name "unconnected-(U1-JTAGSEL-Pad73)") (class "Default")
      (node (ref "U1") (pin "73") (pinfunction "JTAGSEL_73") (pintype "passive"))
    )
    (net (code "93") (name "unconnected-(U1-TST-Pad60)") (class "Default")
      (node (ref "U1") (pin "60") (pinfunction "TST_60") (pintype "passive"))
    )
  )
)
